# USBBreakout-ISO-3_2.net
KiCad netlist of a schematic drawn in EAGLE
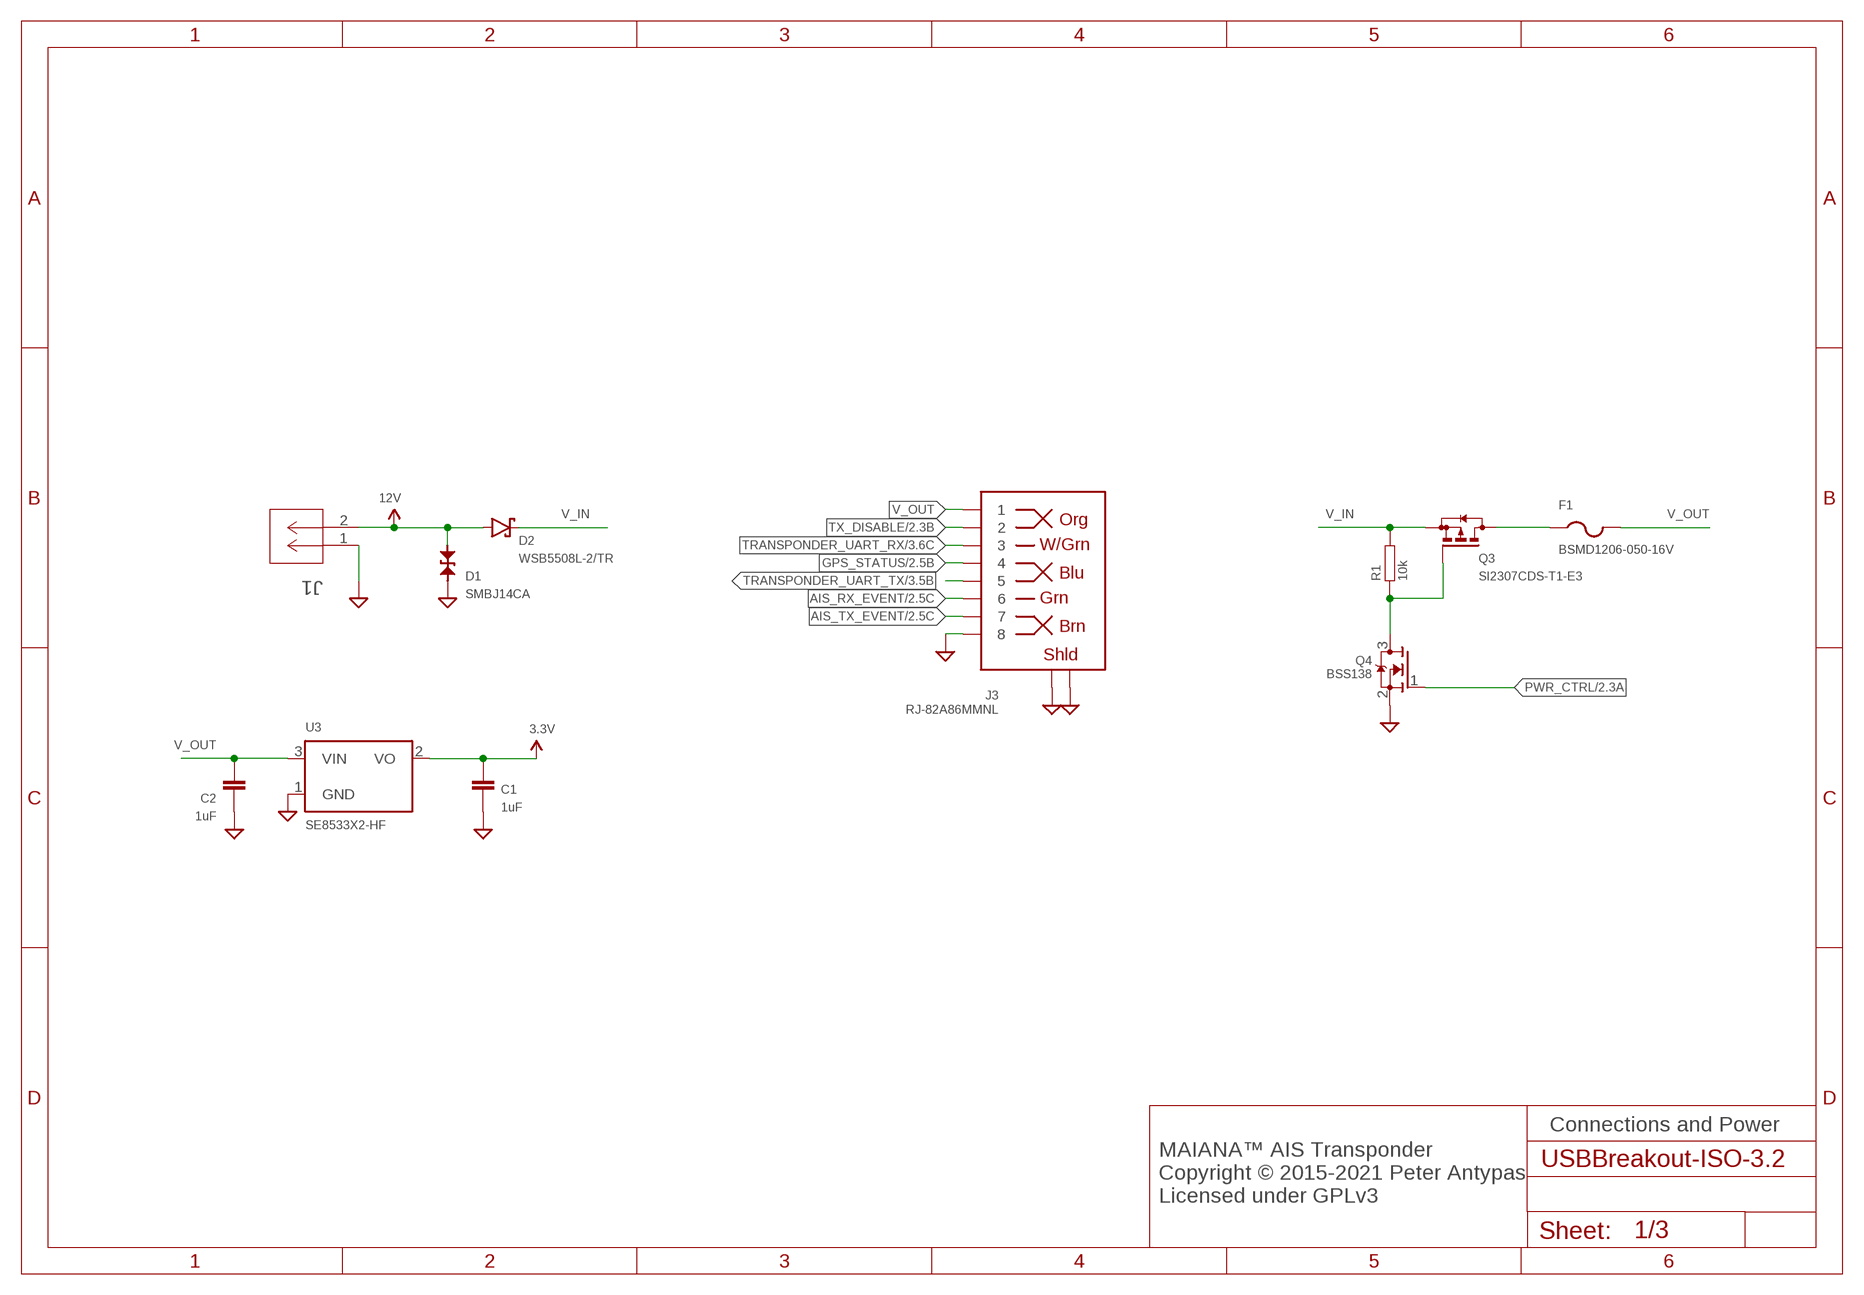
[diagram p0: schematic, sheet 1]
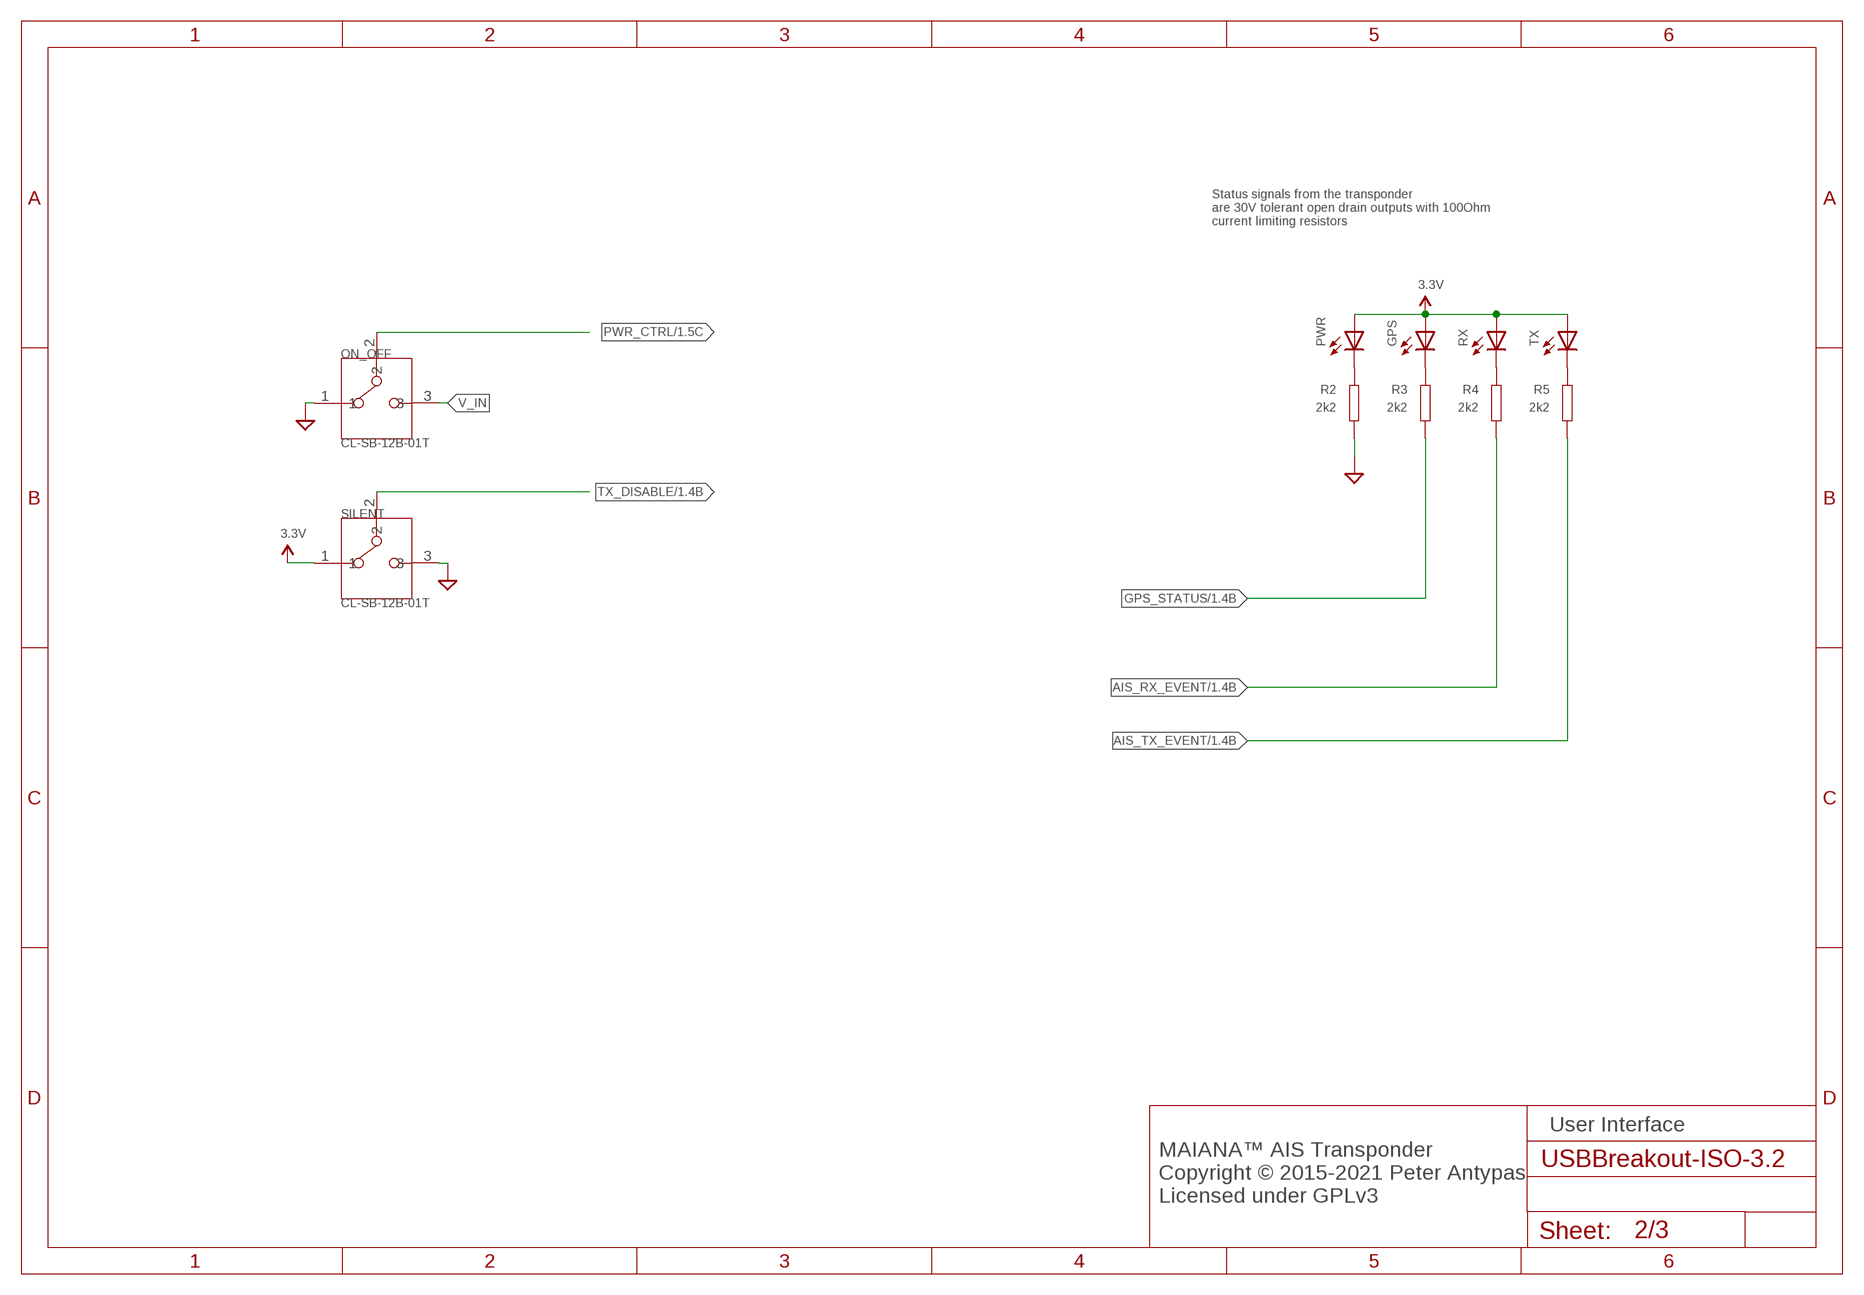
[diagram p1: schematic, sheet 2]
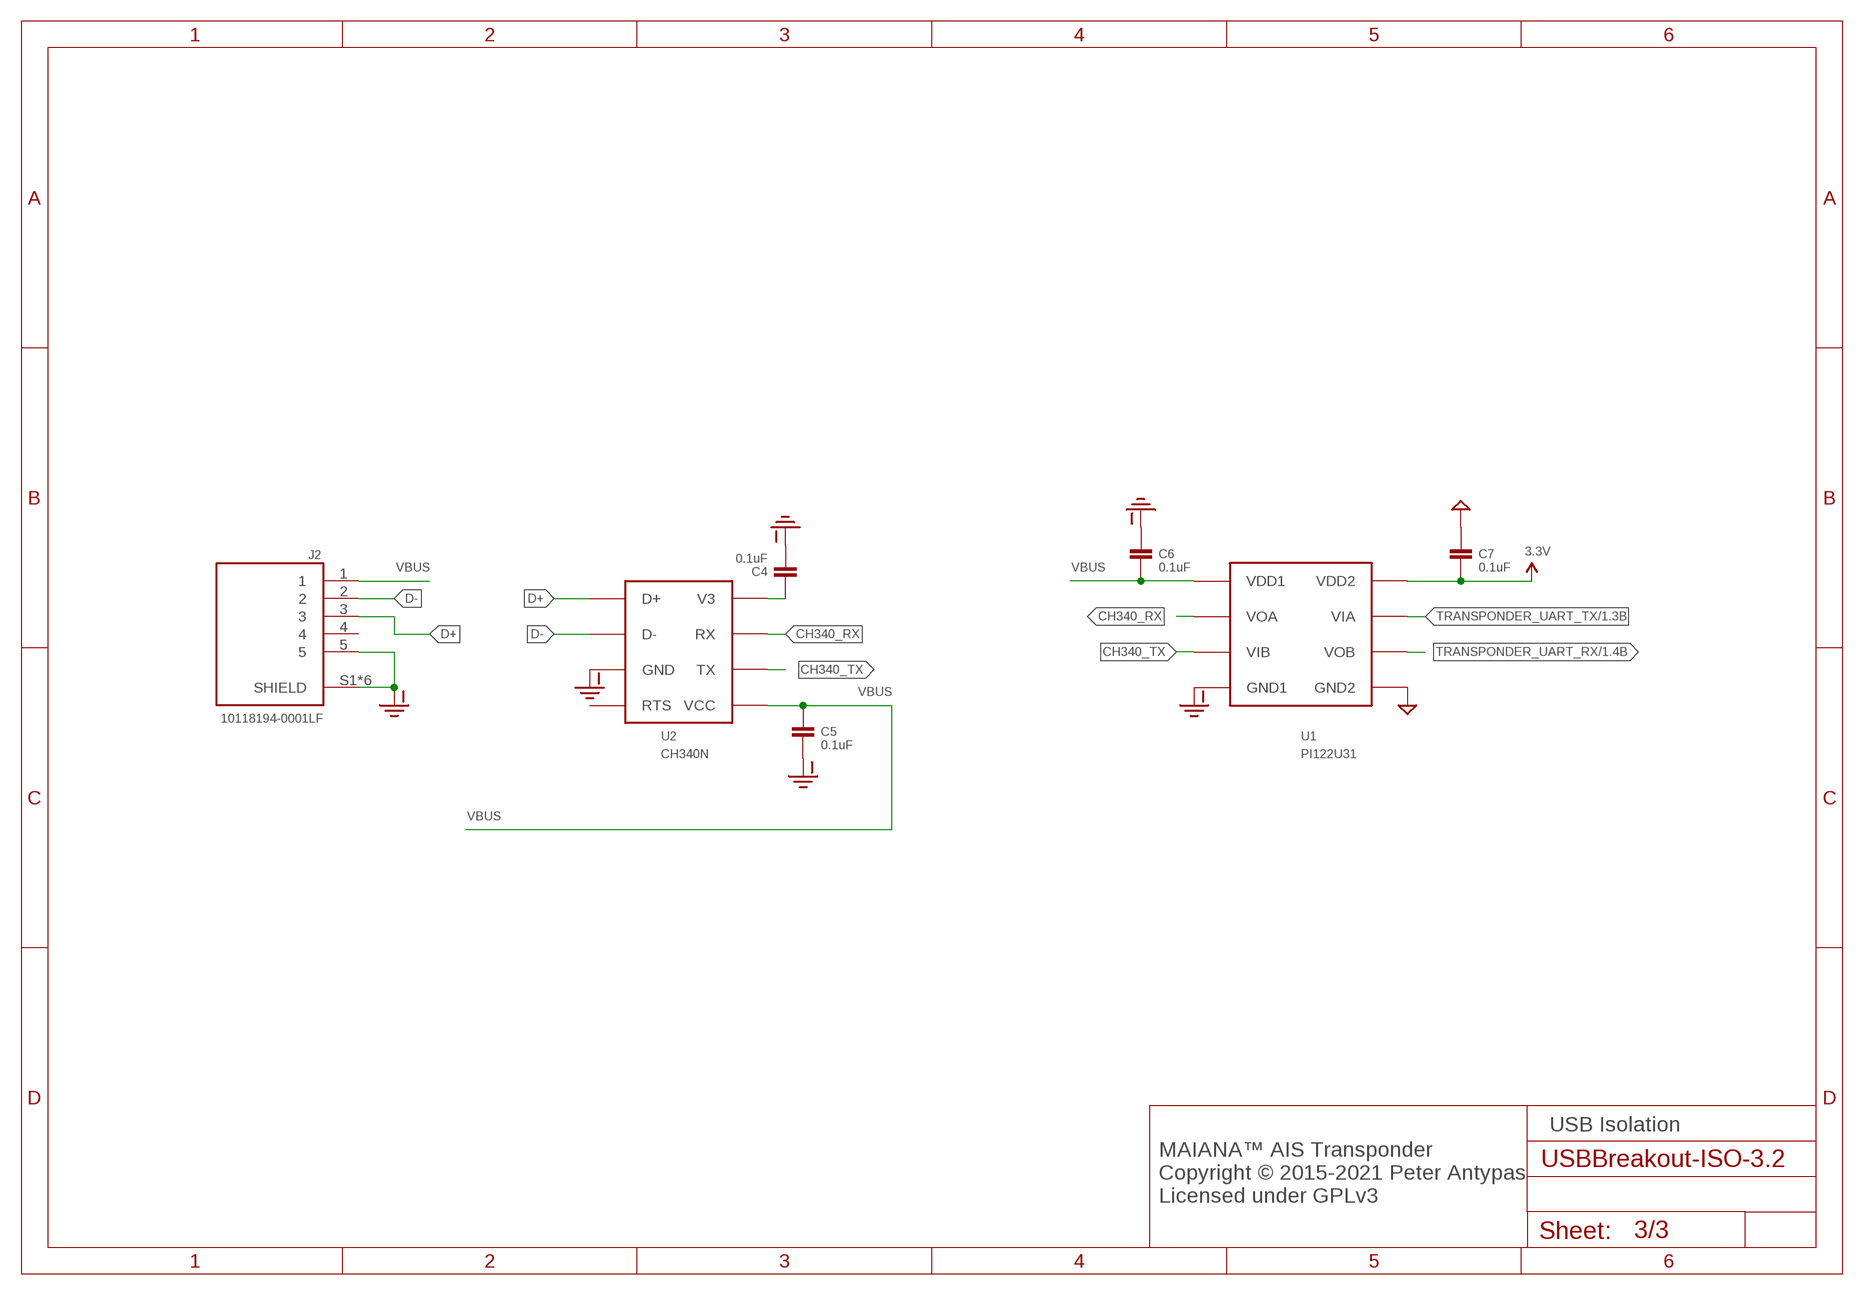
[diagram p2: schematic, sheet 3]

(export (version "E")
  (design (tool "Eeschema 10.0.6"))
  (components
    (comp (ref "GPS")
      (value "LEDCHIPLED_1206")
      (footprint "eagle-import:CHIPLED_1206")
      (fields (field (name "PARTNO") "TJ-S3216CL9T5ALC2G-A5"))
      (libsource (lib "eagle-import") (part "LEDCHIPLED_1206"))
    )
    (comp (ref "ON_OFF")
      (value "CL-SB-12B-01T")
      (footprint "eagle-import:CL-SB-12B")
      (fields (field (name "MF") "Nidec Copal"))
      (libsource (lib "eagle-import") (part "CL-SB-12B-01T"))
    )
    (comp (ref "PWR")
      (value "LEDCHIPLED_1206")
      (footprint "eagle-import:CHIPLED_1206")
      (fields (field (name "PARTNO") "TJ-S3216CL9T5ALC2G-A5"))
      (libsource (lib "eagle-import") (part "LEDCHIPLED_1206"))
    )
    (comp (ref "R2")
      (value "2k2")
      (footprint "eagle-import:0603")
      (fields (field (name "PARTNO") "CR0603-FX-2201ELF"))
      (libsource (lib "eagle-import") (part "RESISTOR0603"))
    )
    (comp (ref "R3")
      (value "2k2")
      (footprint "eagle-import:0603")
      (fields (field (name "PARTNO") "CR0603-FX-2201ELF"))
      (libsource (lib "eagle-import") (part "RESISTOR0603"))
    )
    (comp (ref "R4")
      (value "2k2")
      (footprint "eagle-import:0603")
      (fields (field (name "PARTNO") "CR0603-FX-2201ELF"))
      (libsource (lib "eagle-import") (part "RESISTOR0603"))
    )
    (comp (ref "R5")
      (value "2k2")
      (footprint "eagle-import:0603")
      (fields (field (name "PARTNO") "CR0603-FX-2201ELF"))
      (libsource (lib "eagle-import") (part "RESISTOR0603"))
    )
    (comp (ref "RX")
      (value "LEDCHIPLED_1206")
      (footprint "eagle-import:CHIPLED_1206")
      (fields (field (name "PARTNO") "TJ-S3216CL9T5ALC2G-A5"))
      (libsource (lib "eagle-import") (part "LEDCHIPLED_1206"))
    )
    (comp (ref "SILENT")
      (value "CL-SB-12B-01T")
      (footprint "eagle-import:CL-SB-12B")
      (fields (field (name "MF") "Nidec Copal"))
      (libsource (lib "eagle-import") (part "CL-SB-12B-01T"))
    )
    (comp (ref "TX")
      (value "LEDCHIPLED_1206")
      (footprint "eagle-import:CHIPLED_1206")
      (fields (field (name "PARTNO") "TJ-S3216CL9T5ALC2G-A5"))
      (libsource (lib "eagle-import") (part "LEDCHIPLED_1206"))
    )
    (comp (ref "C4")
      (value "0.1uF")
      (footprint "eagle-import:0603")
      (fields (field (name "PARTNO") "06035C104KAT2A"))
      (libsource (lib "eagle-import") (part "CAPACITOR0603"))
    )
    (comp (ref "C5")
      (value "0.1uF")
      (footprint "eagle-import:0603")
      (fields (field (name "PARTNO") "06035C104KAT2A"))
      (libsource (lib "eagle-import") (part "CAPACITOR0603"))
    )
    (comp (ref "C6")
      (value "0.1uF")
      (footprint "eagle-import:0603")
      (fields (field (name "PARTNO") "06035C104KAT2A"))
      (libsource (lib "eagle-import") (part "CAPACITOR0603"))
    )
    (comp (ref "C7")
      (value "0.1uF")
      (footprint "eagle-import:0603")
      (fields (field (name "PARTNO") "06035C104KAT2A"))
      (libsource (lib "eagle-import") (part "CAPACITOR0603"))
    )
    (comp (ref "J2")
      (value "10118194-0001LF")
      (footprint "eagle-import:AMPHENOL_10118194-0001LF")
      (fields (field (name "MF") "Amphenol ICC (FCI)"))
      (libsource (lib "eagle-import") (part "10118194-0001LF"))
    )
    (comp (ref "U1")
      (value "PI122U31")
      (footprint "eagle-import:SOIC8")
      (fields (field (name "PARTNO") "Pi122U31"))
      (libsource (lib "eagle-import") (part "PI122U3X"))
    )
    (comp (ref "U2")
      (value "CH340N")
      (footprint "eagle-import:SOIC-8")
      (libsource (lib "eagle-import") (part "CH330N"))
    )
    (comp (ref "C1")
      (value "1uF")
      (footprint "eagle-import:0603")
      (fields (field (name "PARTNO") "CC0603KRX5R8BB105"))
      (libsource (lib "eagle-import") (part "CAPACITOR0603"))
    )
    (comp (ref "C2")
      (value "1uF")
      (footprint "eagle-import:0603")
      (fields (field (name "PARTNO") "CC0603KRX5R8BB105"))
      (libsource (lib "eagle-import") (part "CAPACITOR0603"))
    )
    (comp (ref "D1")
      (value "SMBJ14CA")
      (footprint "eagle-import:SMB-BIDIR")
      (fields (field (name "PARTNO") "SMBJ14CA"))
      (libsource (lib "eagle-import") (part "DIODE-TVS-BIDIRSMB"))
    )
    (comp (ref "D2")
      (value "WSB5508L-2/TR")
      (footprint "eagle-import:SOD123")
      (fields (field (name "PARTNO") "WSB5508L-2/TR"))
      (libsource (lib "eagle-import") (part "DIODE-SCHOTTKYSOD123"))
    )
    (comp (ref "F1")
      (value "BSMD1206-050-16V")
      (footprint "eagle-import:R1206")
      (libsource (lib "eagle-import") (part "PTCFUSE-1206"))
    )
    (comp (ref "J1")
      (value "OSTVN02A150")
      (footprint "eagle-import:CONN_OSTVN02A150_OST")
      (fields (field (name "COPYRIGHT") "Copyright (C) 2018 Accelerated Designs. All rights reserved"))
      (libsource (lib "eagle-import") (part "OSTVN02A150"))
    )
    (comp (ref "J3")
      (value "RJ-82A86MMNL")
      (footprint "eagle-import:RJ-82A86MMNL")
      (libsource (lib "eagle-import") (part "RJ-82A86MMNL"))
    )
    (comp (ref "Q3")
      (value "SI2307CDS-T1-E3")
      (footprint "eagle-import:SOT23")
      (libsource (lib "eagle-import") (part "BSS84"))
    )
    (comp (ref "Q4")
      (value "BSS138")
      (footprint "eagle-import:SOT23")
      (libsource (lib "eagle-import") (part "MOSFET-NREFLOW"))
    )
    (comp (ref "R1")
      (value "10k")
      (footprint "eagle-import:0603")
      (fields (field (name "PARTNO") "RC0603FR-0710KL"))
      (libsource (lib "eagle-import") (part "RESISTOR0603"))
    )
    (comp (ref "U3")
      (value "SE8533X2-HF")
      (footprint "eagle-import:SOT23")
      (libsource (lib "eagle-import") (part "MCP1799T"))
    )
  )
  (nets
    (net (code "1") (name "3.3V") (class "Default")
      (node (ref "C1") (pin "P$1") (pinfunction "1_P$1") (pintype "passive"))
      (node (ref "C7") (pin "P$2") (pinfunction "2_P$2") (pintype "passive"))
      (node (ref "GPS") (pin "A") (pinfunction "A_A") (pintype "passive"))
      (node (ref "PWR") (pin "A") (pinfunction "A_A") (pintype "passive"))
      (node (ref "RX") (pin "A") (pinfunction "A_A") (pintype "passive"))
      (node (ref "SILENT") (pin "1") (pinfunction "1_1") (pintype "bidirectional"))
      (node (ref "TX") (pin "A") (pinfunction "A_A") (pintype "passive"))
      (node (ref "U1") (pin "8") (pinfunction "VDD2_8") (pintype "bidirectional"))
      (node (ref "U3") (pin "2") (pinfunction "VO_2") (pintype "output"))
    )
    (net (code "2") (name "12V") (class "Default")
      (node (ref "D1") (pin "A") (pinfunction "P$1_A") (pintype "bidirectional"))
      (node (ref "D2") (pin "A") (pinfunction "A_A") (pintype "passive"))
      (node (ref "J1") (pin "2") (pinfunction "2_2") (pintype "passive"))
    )
    (net (code "3") (name "AIS_RX_EVENT") (class "Default")
      (node (ref "J3") (pin "P$6") (pinfunction "6_P$6") (pintype "bidirectional"))
      (node (ref "R4") (pin "P$2") (pinfunction "P$2_P$2") (pintype "passive"))
    )
    (net (code "4") (name "AIS_TX_EVENT") (class "Default")
      (node (ref "J3") (pin "P$7") (pinfunction "7_P$7") (pintype "bidirectional"))
      (node (ref "R5") (pin "P$2") (pinfunction "P$2_P$2") (pintype "passive"))
    )
    (net (code "5") (name "CH340_RX") (class "Default")
      (node (ref "U1") (pin "2") (pinfunction "VOA_2") (pintype "bidirectional"))
      (node (ref "U2") (pin "7") (pinfunction "RX_7") (pintype "bidirectional"))
    )
    (net (code "6") (name "CH340_TX") (class "Default")
      (node (ref "U1") (pin "3") (pinfunction "VIB_3") (pintype "bidirectional"))
      (node (ref "U2") (pin "6") (pinfunction "TX_6") (pintype "bidirectional"))
    )
    (net (code "7") (name "D+") (class "Default")
      (node (ref "J2") (pin "3") (pinfunction "3_3") (pintype "passive"))
      (node (ref "U2") (pin "1") (pinfunction "D+_1") (pintype "bidirectional"))
    )
    (net (code "8") (name "D-") (class "Default")
      (node (ref "J2") (pin "2") (pinfunction "2_2") (pintype "passive"))
      (node (ref "U2") (pin "2") (pinfunction "D-_2") (pintype "bidirectional"))
    )
    (net (code "9") (name "GND") (class "Default")
      (node (ref "C1") (pin "P$2") (pinfunction "2_P$2") (pintype "passive"))
      (node (ref "C2") (pin "P$2") (pinfunction "2_P$2") (pintype "passive"))
      (node (ref "C7") (pin "P$1") (pinfunction "1_P$1") (pintype "passive"))
      (node (ref "D1") (pin "C") (pinfunction "P$2_C") (pintype "bidirectional"))
      (node (ref "J1") (pin "1") (pinfunction "1_1") (pintype "passive"))
      (node (ref "J3") (pin "P$10") (pinfunction "SHLD_P$10") (pintype "bidirectional"))
      (node (ref "J3") (pin "P$11") (pinfunction "SHLD_P$11") (pintype "bidirectional"))
      (node (ref "J3") (pin "P$12") (pinfunction "SHLD_P$12") (pintype "bidirectional"))
      (node (ref "J3") (pin "P$8") (pinfunction "8_P$8") (pintype "bidirectional"))
      (node (ref "J3") (pin "P$9") (pinfunction "SHLD_P$9") (pintype "bidirectional"))
      (node (ref "ON_OFF") (pin "1") (pinfunction "1_1") (pintype "bidirectional"))
      (node (ref "Q4") (pin "2") (pinfunction "S_2") (pintype "bidirectional"))
      (node (ref "R2") (pin "P$2") (pinfunction "P$2_P$2") (pintype "passive"))
      (node (ref "SILENT") (pin "3") (pinfunction "3_3") (pintype "bidirectional"))
      (node (ref "U1") (pin "5") (pinfunction "GND2_5") (pintype "bidirectional"))
      (node (ref "U3") (pin "1") (pinfunction "GND_1") (pintype "passive"))
    )
    (net (code "10") (name "GND-ISO") (class "Default")
      (node (ref "C4") (pin "P$2") (pinfunction "2_P$2") (pintype "passive"))
      (node (ref "C5") (pin "P$2") (pinfunction "2_P$2") (pintype "passive"))
      (node (ref "C6") (pin "P$1") (pinfunction "1_P$1") (pintype "passive"))
      (node (ref "J2") (pin "5") (pinfunction "5_5") (pintype "passive"))
      (node (ref "J2") (pin "S1") (pinfunction "SHIELD_S1") (pintype "passive"))
      (node (ref "J2") (pin "S2") (pinfunction "SHIELD_S2") (pintype "passive"))
      (node (ref "J2") (pin "S3") (pinfunction "SHIELD_S3") (pintype "passive"))
      (node (ref "J2") (pin "S4") (pinfunction "SHIELD_S4") (pintype "passive"))
      (node (ref "J2") (pin "S5") (pinfunction "SHIELD_S5") (pintype "passive"))
      (node (ref "J2") (pin "S6") (pinfunction "SHIELD_S6") (pintype "passive"))
      (node (ref "U1") (pin "4") (pinfunction "GND1_4") (pintype "bidirectional"))
      (node (ref "U2") (pin "3") (pinfunction "GND_3") (pintype "bidirectional"))
    )
    (net (code "11") (name "GPS_STATUS") (class "Default")
      (node (ref "J3") (pin "P$4") (pinfunction "4_P$4") (pintype "bidirectional"))
      (node (ref "R3") (pin "P$2") (pinfunction "P$2_P$2") (pintype "passive"))
    )
    (net (code "12") (name "Net-(C4-1)") (class "Default")
      (node (ref "C4") (pin "P$1") (pinfunction "1_P$1") (pintype "passive"))
      (node (ref "U2") (pin "8") (pinfunction "V3_8") (pintype "bidirectional"))
    )
    (net (code "13") (name "Net-(GPS-PadC)") (class "Default")
      (node (ref "GPS") (pin "C") (pinfunction "C_C") (pintype "passive"))
      (node (ref "R3") (pin "P$1") (pinfunction "P$1_P$1") (pintype "passive"))
    )
    (net (code "14") (name "Net-(PWR-PadC)") (class "Default")
      (node (ref "PWR") (pin "C") (pinfunction "C_C") (pintype "passive"))
      (node (ref "R2") (pin "P$1") (pinfunction "P$1_P$1") (pintype "passive"))
    )
    (net (code "15") (name "Net-(Q3-D)") (class "Default")
      (node (ref "F1") (pin "1") (pinfunction "1_1") (pintype "passive"))
      (node (ref "Q3") (pin "3") (pinfunction "D_3") (pintype "passive"))
    )
    (net (code "16") (name "Net-(Q3-G)") (class "Default")
      (node (ref "Q3") (pin "1") (pinfunction "G_1") (pintype "passive"))
      (node (ref "Q4") (pin "3") (pinfunction "D_3") (pintype "bidirectional"))
      (node (ref "R1") (pin "P$1") (pinfunction "P$1_P$1") (pintype "passive"))
    )
    (net (code "17") (name "Net-(R4-PadP$1)") (class "Default")
      (node (ref "R4") (pin "P$1") (pinfunction "P$1_P$1") (pintype "passive"))
      (node (ref "RX") (pin "C") (pinfunction "C_C") (pintype "passive"))
    )
    (net (code "18") (name "Net-(R5-PadP$1)") (class "Default")
      (node (ref "R5") (pin "P$1") (pinfunction "P$1_P$1") (pintype "passive"))
      (node (ref "TX") (pin "C") (pinfunction "C_C") (pintype "passive"))
    )
    (net (code "19") (name "PWR_CTRL") (class "Default")
      (node (ref "ON_OFF") (pin "2") (pinfunction "2_2") (pintype "bidirectional"))
      (node (ref "Q4") (pin "1") (pinfunction "G_1") (pintype "bidirectional"))
    )
    (net (code "20") (name "TRANSPONDER_UART_RX") (class "Default")
      (node (ref "J3") (pin "P$3") (pinfunction "3_P$3") (pintype "bidirectional"))
      (node (ref "U1") (pin "6") (pinfunction "VOB_6") (pintype "bidirectional"))
    )
    (net (code "21") (name "TRANSPONDER_UART_TX") (class "Default")
      (node (ref "J3") (pin "P$5") (pinfunction "5_P$5") (pintype "bidirectional"))
      (node (ref "U1") (pin "7") (pinfunction "VIA_7") (pintype "bidirectional"))
    )
    (net (code "22") (name "TX_DISABLE") (class "Default")
      (node (ref "J3") (pin "P$2") (pinfunction "2_P$2") (pintype "bidirectional"))
      (node (ref "SILENT") (pin "2") (pinfunction "2_2") (pintype "bidirectional"))
    )
    (net (code "23") (name "VBUS") (class "Default")
      (node (ref "C5") (pin "P$1") (pinfunction "1_P$1") (pintype "passive"))
      (node (ref "C6") (pin "P$2") (pinfunction "2_P$2") (pintype "passive"))
      (node (ref "J2") (pin "1") (pinfunction "1_1") (pintype "passive"))
      (node (ref "U1") (pin "1") (pinfunction "VDD1_1") (pintype "bidirectional"))
      (node (ref "U2") (pin "5") (pinfunction "VCC_5") (pintype "bidirectional"))
    )
    (net (code "24") (name "V_IN") (class "Default")
      (node (ref "D2") (pin "C") (pinfunction "C_C") (pintype "passive"))
      (node (ref "ON_OFF") (pin "3") (pinfunction "3_3") (pintype "bidirectional"))
      (node (ref "Q3") (pin "2") (pinfunction "S_2") (pintype "passive"))
      (node (ref "R1") (pin "P$2") (pinfunction "P$2_P$2") (pintype "passive"))
    )
    (net (code "25") (name "V_OUT") (class "Default")
      (node (ref "C2") (pin "P$1") (pinfunction "1_P$1") (pintype "passive"))
      (node (ref "F1") (pin "2") (pinfunction "2_2") (pintype "passive"))
      (node (ref "J3") (pin "P$1") (pinfunction "1_P$1") (pintype "bidirectional"))
      (node (ref "U3") (pin "3") (pinfunction "VIN_3") (pintype "input"))
    )
    (net (code "26") (name "unconnected-(J2-Pad4)") (class "Default")
      (node (ref "J2") (pin "4") (pinfunction "4_4") (pintype "passive"))
    )
    (net (code "27") (name "unconnected-(U2-RTS-Pad4)") (class "Default")
      (node (ref "U2") (pin "4") (pinfunction "RTS_4") (pintype "bidirectional"))
    )
  )
)
